# Interface_exp.net
KiCad netlist of a schematic drawn in Altium Designer
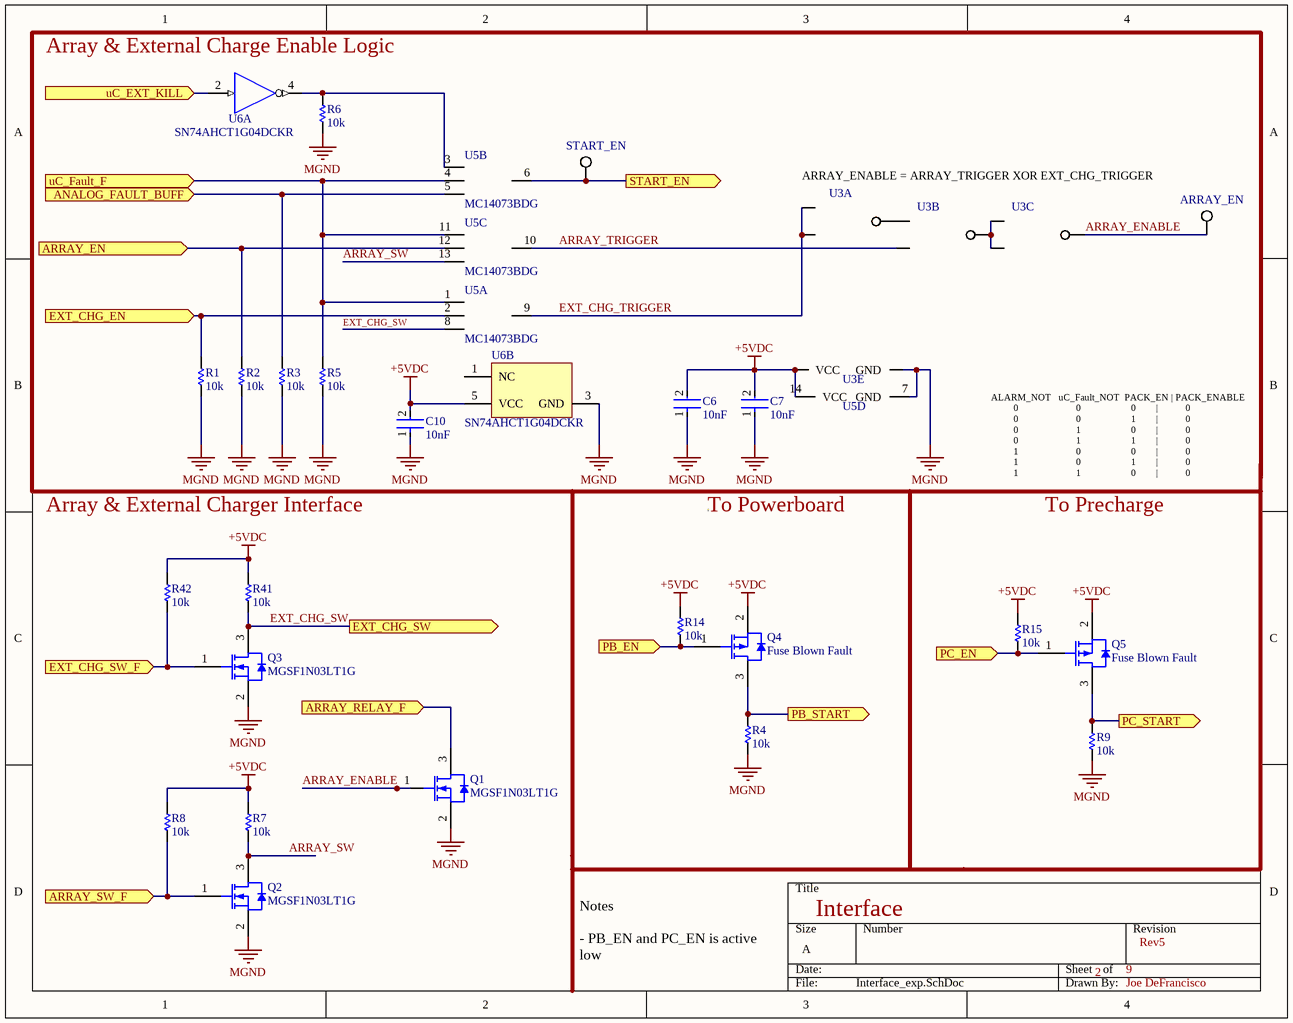
[diagram p0: Interface_exp.SchDoc]

(export (version "E")
  (design (tool "Eeschema 10.0.6"))
  (components
    (comp (ref "ARRAY_EN")
      (value "Test Point")
      (footprint "Test Point")
      (libsource (lib "PrISUm-Connectors") (part "Test Point"))
    )
    (comp (ref "C6")
      (value "CGA3E2X8R2A103K080AD")
      (footprint "FP-CGA3E-0_3-0_1-IPC_A")
      (description "Cap Ceramic 10nF 100V X8R 10% Pad SMD 0603 +150°C Automotive T/R")
      (fields (field (name "CAPACITANCE") "10nF") (field (name "TOLERANCE") "10%"))
      (libsource (lib "Altium Content Vault") (part "b4654b650e69147ec39a6b967a45e02"))
    )
    (comp (ref "C7")
      (value "CGA3E2X8R2A103K080AD")
      (footprint "FP-CGA3E-0_3-0_1-IPC_A")
      (description "Cap Ceramic 10nF 100V X8R 10% Pad SMD 0603 +150°C Automotive T/R")
      (fields (field (name "CAPACITANCE") "10nF") (field (name "TOLERANCE") "10%"))
      (libsource (lib "Altium Content Vault") (part "b4654b650e69147ec39a6b967a45e02"))
    )
    (comp (ref "C10")
      (value "CGA3E2X8R2A103K080AD")
      (footprint "FP-CGA3E-0_3-0_1-IPC_A")
      (description "Cap Ceramic 10nF 100V X8R 10% Pad SMD 0603 +150°C Automotive T/R")
      (fields (field (name "CAPACITANCE") "10nF") (field (name "TOLERANCE") "10%"))
      (libsource (lib "Altium Content Vault") (part "b4654b650e69147ec39a6b967a45e02"))
    )
    (comp (ref "Q1")
      (value "MGSF1N03LT1G")
      (footprint "ONSC-SOT-23-3-318-08_V")
      (description "Power MOSFET, 30 V, 2.1 A, Single N-Channel, 3-Pin SOT-23, Pb-Free, Tape and Reel")
      (fields (field (name "MANUFACTURER") "On Semiconductor"))
      (libsource (lib "Altium Content Vault") (part "ONSC-NMOS-G1S2D3-3"))
    )
    (comp (ref "Q2")
      (value "MGSF1N03LT1G")
      (footprint "ONSC-SOT-23-3-318-08_V")
      (description "Power MOSFET, 30 V, 2.1 A, Single N-Channel, 3-Pin SOT-23, Pb-Free, Tape and Reel")
      (fields (field (name "MANUFACTURER") "On Semiconductor"))
      (libsource (lib "Altium Content Vault") (part "ONSC-NMOS-G1S2D3-3"))
    )
    (comp (ref "Q3")
      (value "MGSF1N03LT1G")
      (footprint "ONSC-SOT-23-3-318-08_V")
      (description "Power MOSFET, 30 V, 2.1 A, Single N-Channel, 3-Pin SOT-23, Pb-Free, Tape and Reel")
      (fields (field (name "MANUFACTURER") "On Semiconductor"))
      (libsource (lib "Altium Content Vault") (part "ONSC-NMOS-G1S2D3-3"))
    )
    (comp (ref "Q4")
      (value "Fuse Blown Fault")
      (footprint "INTR-SOT-23-3_V")
      (fields (field (name "MANUFACTURER") "International Rectifier"))
      (libsource (lib "Altium Content Vault") (part "PEMOS-GSD-3"))
    )
    (comp (ref "Q5")
      (value "Fuse Blown Fault")
      (footprint "INTR-SOT-23-3_V")
      (fields (field (name "MANUFACTURER") "International Rectifier"))
      (libsource (lib "Altium Content Vault") (part "PEMOS-GSD-3"))
    )
    (comp (ref "R1")
      (value "RES_10k_1%_0603")
      (footprint "R_0603")
      (fields
        (field (name "MANUFACTURER PART NUMBER") "RC0603FR-0710KL")
        (field (name "MANUFACTURER") "Yageo")
        (field (name "DIGIKEY PART NUMBER") "311-10.0KHRCT-ND")
        (field (name "SCHEMATICINFORMATION") "10k")
      )
      (libsource (lib "Resistors") (part "RES_10k_1%_0603"))
    )
    (comp (ref "R2")
      (value "RES_10k_1%_0603")
      (footprint "R_0603")
      (fields
        (field (name "MANUFACTURER PART NUMBER") "RC0603FR-0710KL")
        (field (name "MANUFACTURER") "Yageo")
        (field (name "DIGIKEY PART NUMBER") "311-10.0KHRCT-ND")
        (field (name "SCHEMATICINFORMATION") "10k")
      )
      (libsource (lib "Resistors") (part "RES_10k_1%_0603"))
    )
    (comp (ref "R3")
      (value "RES_10k_1%_0603")
      (footprint "R_0603")
      (fields
        (field (name "MANUFACTURER PART NUMBER") "RC0603FR-0710KL")
        (field (name "MANUFACTURER") "Yageo")
        (field (name "DIGIKEY PART NUMBER") "311-10.0KHRCT-ND")
        (field (name "SCHEMATICINFORMATION") "10k")
      )
      (libsource (lib "Resistors") (part "RES_10k_1%_0603"))
    )
    (comp (ref "R4")
      (value "RES_10k_1%_0603")
      (footprint "R_0603")
      (fields
        (field (name "MANUFACTURER PART NUMBER") "RC0603FR-0710KL")
        (field (name "MANUFACTURER") "Yageo")
        (field (name "DIGIKEY PART NUMBER") "311-10.0KHRCT-ND")
        (field (name "SCHEMATICINFORMATION") "10k")
      )
      (libsource (lib "Resistors") (part "RES_10k_1%_0603"))
    )
    (comp (ref "R5")
      (value "RES_10k_1%_0603")
      (footprint "R_0603")
      (fields
        (field (name "MANUFACTURER PART NUMBER") "RC0603FR-0710KL")
        (field (name "MANUFACTURER") "Yageo")
        (field (name "DIGIKEY PART NUMBER") "311-10.0KHRCT-ND")
        (field (name "SCHEMATICINFORMATION") "10k")
      )
      (libsource (lib "Resistors") (part "RES_10k_1%_0603"))
    )
    (comp (ref "R6")
      (value "RES_10k_1%_0603")
      (footprint "R_0603")
      (fields
        (field (name "MANUFACTURER PART NUMBER") "RC0603FR-0710KL")
        (field (name "MANUFACTURER") "Yageo")
        (field (name "DIGIKEY PART NUMBER") "311-10.0KHRCT-ND")
        (field (name "SCHEMATICINFORMATION") "10k")
      )
      (libsource (lib "Resistors") (part "RES_10k_1%_0603"))
    )
    (comp (ref "R7")
      (value "RES_10k_1%_0603")
      (footprint "R_0603")
      (fields
        (field (name "MANUFACTURER PART NUMBER") "RC0603FR-0710KL")
        (field (name "MANUFACTURER") "Yageo")
        (field (name "DIGIKEY PART NUMBER") "311-10.0KHRCT-ND")
        (field (name "SCHEMATICINFORMATION") "10k")
      )
      (libsource (lib "Resistors") (part "RES_10k_1%_0603"))
    )
    (comp (ref "R8")
      (value "RES_10k_1%_0603")
      (footprint "R_0603")
      (fields
        (field (name "MANUFACTURER PART NUMBER") "RC0603FR-0710KL")
        (field (name "MANUFACTURER") "Yageo")
        (field (name "DIGIKEY PART NUMBER") "311-10.0KHRCT-ND")
        (field (name "SCHEMATICINFORMATION") "10k")
      )
      (libsource (lib "Resistors") (part "RES_10k_1%_0603"))
    )
    (comp (ref "R9")
      (value "RES_10k_1%_0603")
      (footprint "R_0603")
      (fields
        (field (name "MANUFACTURER PART NUMBER") "RC0603FR-0710KL")
        (field (name "MANUFACTURER") "Yageo")
        (field (name "DIGIKEY PART NUMBER") "311-10.0KHRCT-ND")
        (field (name "SCHEMATICINFORMATION") "10k")
      )
      (libsource (lib "Resistors") (part "RES_10k_1%_0603"))
    )
    (comp (ref "R14")
      (value "RES_10k_1%_0603")
      (footprint "R_0603")
      (fields
        (field (name "MANUFACTURER PART NUMBER") "RC0603FR-0710KL")
        (field (name "MANUFACTURER") "Yageo")
        (field (name "DIGIKEY PART NUMBER") "311-10.0KHRCT-ND")
        (field (name "SCHEMATICINFORMATION") "10k")
      )
      (libsource (lib "Resistors") (part "RES_10k_1%_0603"))
    )
    (comp (ref "R15")
      (value "RES_10k_1%_0603")
      (footprint "R_0603")
      (fields
        (field (name "MANUFACTURER PART NUMBER") "RC0603FR-0710KL")
        (field (name "MANUFACTURER") "Yageo")
        (field (name "DIGIKEY PART NUMBER") "311-10.0KHRCT-ND")
        (field (name "SCHEMATICINFORMATION") "10k")
      )
      (libsource (lib "Resistors") (part "RES_10k_1%_0603"))
    )
    (comp (ref "R41")
      (value "RES_10k_1%_0603")
      (footprint "R_0603")
      (fields
        (field (name "MANUFACTURER PART NUMBER") "RC0603FR-0710KL")
        (field (name "MANUFACTURER") "Yageo")
        (field (name "DIGIKEY PART NUMBER") "311-10.0KHRCT-ND")
        (field (name "SCHEMATICINFORMATION") "10k")
      )
      (libsource (lib "Resistors") (part "RES_10k_1%_0603"))
    )
    (comp (ref "R42")
      (value "RES_10k_1%_0603")
      (footprint "R_0603")
      (fields
        (field (name "MANUFACTURER PART NUMBER") "RC0603FR-0710KL")
        (field (name "MANUFACTURER") "Yageo")
        (field (name "DIGIKEY PART NUMBER") "311-10.0KHRCT-ND")
        (field (name "SCHEMATICINFORMATION") "10k")
      )
      (libsource (lib "Resistors") (part "RES_10k_1%_0603"))
    )
    (comp (ref "START_EN")
      (value "Test Point")
      (footprint "Test Point")
      (libsource (lib "BPS") (part "Test Point"))
    )
    (comp (ref "U3")
      (value "Quad NAND Gate - 2 Input")
      (footprint "SO14")
      (description "Quad NAND Gate - 2 Input 74AC00SCX")
      (libsource (lib "BPSHeadNode") (part "NAND Quad 2 Input - 74AC00SCX"))
    )
    (comp (ref "U5")
      (value "MC14073BDG")
      (footprint "SO14")
      (description "Triple 3-Input AND")
      (fields (field (name "DRAWN BY") "Aaron Mills"))
      (libsource (lib "BPSHeadNode") (part "MC14073BDG"))
    )
    (comp (ref "U6")
      (value "SN74AHCT1G04DCKR")
      (footprint "DCK0005A_L")
      (description "Single Inverter Gate, DCK0005A, LARGE T&R")
      (fields
        (field (name "MANUFACTURER") "Texas Instruments")
        (field (name "GENERIC PART NUMBER") "SN74AHCT1G04")
      )
      (libsource (lib "Altium Content Vault") (part "TI-SN74XXX1XX4-XX-5"))
    )
  )
  (nets
    (net (code "1") (name "+5VDC") (class "Default")
      (node (ref "C10") (pin "2") (pinfunction "2_2") (pintype "passive"))
      (node (ref "C6") (pin "2") (pinfunction "2_2") (pintype "passive"))
      (node (ref "C7") (pin "2") (pinfunction "2_2") (pintype "passive"))
      (node (ref "Q4") (pin "2") (pinfunction "SOURCE_2") (pintype "passive"))
      (node (ref "Q5") (pin "2") (pinfunction "SOURCE_2") (pintype "passive"))
      (node (ref "R14") (pin "1") (pinfunction "1_1") (pintype "passive"))
      (node (ref "R15") (pin "1") (pinfunction "1_1") (pintype "passive"))
      (node (ref "R41") (pin "1") (pinfunction "1_1") (pintype "passive"))
      (node (ref "R42") (pin "1") (pinfunction "1_1") (pintype "passive"))
      (node (ref "R7") (pin "1") (pinfunction "1_1") (pintype "passive"))
      (node (ref "R8") (pin "1") (pinfunction "1_1") (pintype "passive"))
      (node (ref "U3") (pin "14") (pinfunction "VCC_14") (pintype "passive"))
      (node (ref "U5") (pin "14") (pinfunction "VCC_14") (pintype "passive"))
      (node (ref "U6") (pin "5") (pinfunction "VCC_5") (pintype "power_in"))
    )
    (net (code "2") (name "/ANALOG_FAULT_BUFF") (class "Default")
      (node (ref "R3") (pin "1") (pinfunction "1_1") (pintype "passive"))
      (node (ref "U5") (pin "5") (pintype "passive"))
    )
    (net (code "3") (name "/ARRAY_EN") (class "Default")
      (node (ref "R2") (pin "1") (pinfunction "1_1") (pintype "passive"))
      (node (ref "U5") (pin "12") (pintype "passive"))
    )
    (net (code "4") (name "/ARRAY_ENABLE") (class "Default")
      (node (ref "ARRAY_EN") (pin "1") (pinfunction "1_1") (pintype "passive"))
      (node (ref "Q1") (pin "1") (pinfunction "G_1") (pintype "passive"))
      (node (ref "U3") (pin "8") (pinfunction "8_8") (pintype "passive"))
    )
    (net (code "5") (name "/ARRAY_RELAY_F") (class "Default")
      (node (ref "Q1") (pin "3") (pinfunction "D_3") (pintype "passive"))
    )
    (net (code "6") (name "/ARRAY_SW") (class "Default")
      (node (ref "Q2") (pin "3") (pinfunction "D_3") (pintype "passive"))
      (node (ref "R7") (pin "2") (pinfunction "2_2") (pintype "passive"))
      (node (ref "U5") (pin "13") (pintype "passive"))
    )
    (net (code "7") (name "/ARRAY_SW_F") (class "Default")
      (node (ref "Q2") (pin "1") (pinfunction "G_1") (pintype "passive"))
      (node (ref "R8") (pin "2") (pinfunction "2_2") (pintype "passive"))
    )
    (net (code "8") (name "/ARRAY_TRIGGER") (class "Default")
      (node (ref "U3") (pin "5") (pinfunction "5_5") (pintype "passive"))
      (node (ref "U5") (pin "10") (pintype "passive"))
    )
    (net (code "9") (name "/EXT_CHG_EN") (class "Default")
      (node (ref "R1") (pin "1") (pinfunction "1_1") (pintype "passive"))
      (node (ref "U5") (pin "2") (pintype "passive"))
    )
    (net (code "10") (name "/EXT_CHG_SW") (class "Default")
      (node (ref "Q3") (pin "3") (pinfunction "D_3") (pintype "passive"))
      (node (ref "R41") (pin "2") (pinfunction "2_2") (pintype "passive"))
      (node (ref "U5") (pin "8") (pintype "passive"))
    )
    (net (code "11") (name "/EXT_CHG_SW_F") (class "Default")
      (node (ref "Q3") (pin "1") (pinfunction "G_1") (pintype "passive"))
      (node (ref "R42") (pin "2") (pinfunction "2_2") (pintype "passive"))
    )
    (net (code "12") (name "/EXT_CHG_TRIGGER") (class "Default")
      (node (ref "U3") (pin "1") (pinfunction "1_1") (pintype "passive"))
      (node (ref "U3") (pin "2") (pinfunction "2_2") (pintype "passive"))
      (node (ref "U5") (pin "9") (pintype "passive"))
    )
    (net (code "13") (name "/PB_EN") (class "Default")
      (node (ref "Q4") (pin "1") (pinfunction "GATE_1") (pintype "passive"))
      (node (ref "R14") (pin "2") (pinfunction "2_2") (pintype "passive"))
    )
    (net (code "14") (name "/PB_START") (class "Default")
      (node (ref "Q4") (pin "3") (pinfunction "DRAIN_3") (pintype "passive"))
      (node (ref "R4") (pin "1") (pinfunction "1_1") (pintype "passive"))
    )
    (net (code "15") (name "/PC_EN") (class "Default")
      (node (ref "Q5") (pin "1") (pinfunction "GATE_1") (pintype "passive"))
      (node (ref "R15") (pin "2") (pinfunction "2_2") (pintype "passive"))
    )
    (net (code "16") (name "/PC_START") (class "Default")
      (node (ref "Q5") (pin "3") (pinfunction "DRAIN_3") (pintype "passive"))
      (node (ref "R9") (pin "1") (pinfunction "1_1") (pintype "passive"))
    )
    (net (code "17") (name "/START_EN") (class "Default")
      (node (ref "START_EN") (pin "1") (pinfunction "1_1") (pintype "passive"))
      (node (ref "U5") (pin "6") (pintype "passive"))
    )
    (net (code "18") (name "/uC_EXT_KILL") (class "Default")
      (node (ref "U6") (pin "2") (pinfunction "A_2") (pintype "input"))
    )
    (net (code "19") (name "/uC_Fault_F") (class "Default")
      (node (ref "R5") (pin "1") (pinfunction "1_1") (pintype "passive"))
      (node (ref "U5") (pin "1") (pintype "passive"))
      (node (ref "U5") (pin "11") (pintype "passive"))
      (node (ref "U5") (pin "4") (pintype "passive"))
    )
    (net (code "20") (name "MGND") (class "Default")
      (node (ref "C10") (pin "1") (pinfunction "1_1") (pintype "passive"))
      (node (ref "C6") (pin "1") (pinfunction "1_1") (pintype "passive"))
      (node (ref "C7") (pin "1") (pinfunction "1_1") (pintype "passive"))
      (node (ref "Q1") (pin "2") (pinfunction "S_2") (pintype "passive"))
      (node (ref "Q2") (pin "2") (pinfunction "S_2") (pintype "passive"))
      (node (ref "Q3") (pin "2") (pinfunction "S_2") (pintype "passive"))
      (node (ref "R1") (pin "2") (pinfunction "2_2") (pintype "passive"))
      (node (ref "R2") (pin "2") (pinfunction "2_2") (pintype "passive"))
      (node (ref "R3") (pin "2") (pinfunction "2_2") (pintype "passive"))
      (node (ref "R4") (pin "2") (pinfunction "2_2") (pintype "passive"))
      (node (ref "R5") (pin "2") (pinfunction "2_2") (pintype "passive"))
      (node (ref "R6") (pin "2") (pinfunction "2_2") (pintype "passive"))
      (node (ref "R9") (pin "2") (pinfunction "2_2") (pintype "passive"))
      (node (ref "U3") (pin "7") (pinfunction "GND_7") (pintype "passive"))
      (node (ref "U5") (pin "7") (pinfunction "GND_7") (pintype "passive"))
      (node (ref "U6") (pin "3") (pinfunction "GND_3") (pintype "power_in"))
    )
    (net (code "21") (name "Net-(U3-Pad3)") (class "Default")
      (node (ref "U3") (pin "3") (pinfunction "3_3") (pintype "passive"))
      (node (ref "U3") (pin "4") (pinfunction "4_4") (pintype "passive"))
    )
    (net (code "22") (name "Net-(U3-Pad10)") (class "Default")
      (node (ref "U3") (pin "10") (pinfunction "10_10") (pintype "passive"))
      (node (ref "U3") (pin "6") (pinfunction "6_6") (pintype "passive"))
      (node (ref "U3") (pin "9") (pinfunction "9_9") (pintype "passive"))
    )
    (net (code "23") (name "Net-(U6A-Y)") (class "Default")
      (node (ref "R6") (pin "1") (pinfunction "1_1") (pintype "passive"))
      (node (ref "U5") (pin "3") (pintype "passive"))
      (node (ref "U6") (pin "4") (pinfunction "Y_4") (pintype "output"))
    )
    (net (code "24") (name "unconnected-(U6B-NC-Pad1)") (class "Default")
      (node (ref "U6") (pin "1") (pinfunction "NC_1") (pintype "passive"))
    )
  )
)
